# AFM_Power_board__NEW.net
KiCad netlist of a schematic drawn in EAGLE
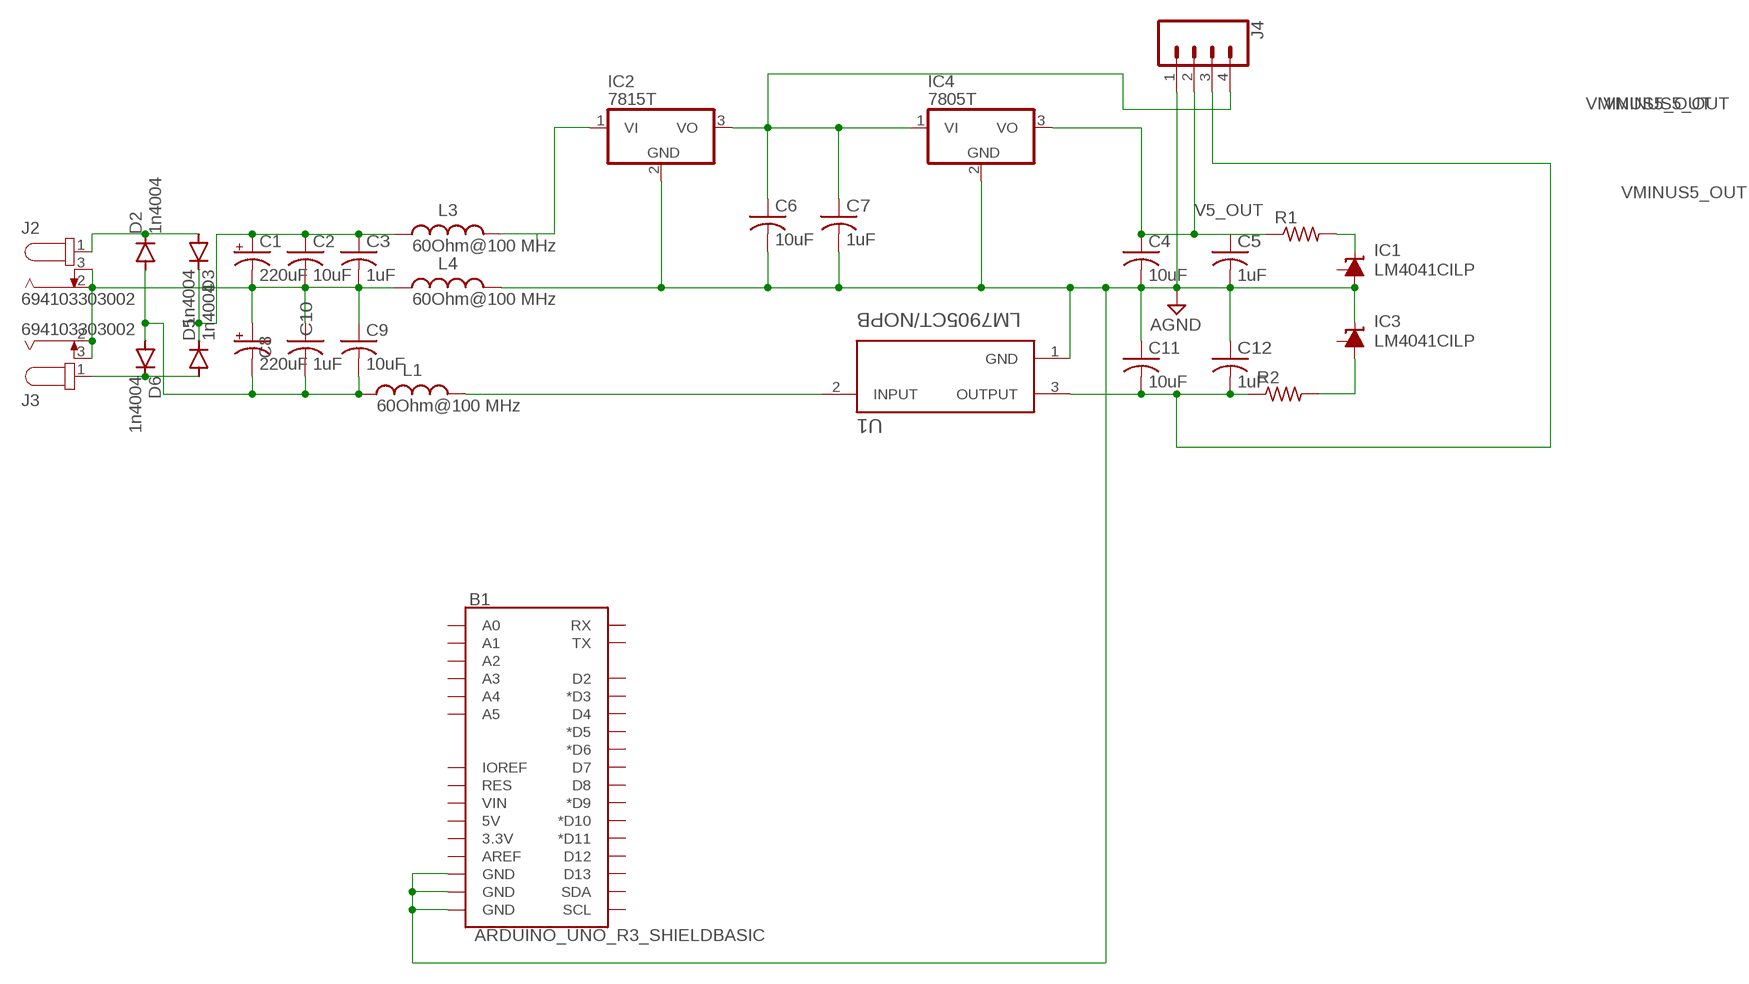
[diagram p0: schematic, sheet 1]

(export (version "E")
  (design (tool "Eeschema 10.0.6"))
  (components
    (comp (ref "B1")
      (value "ARDUINO_UNO_R3_SHIELDBASIC")
      (footprint "eagle-import:UNO_R3_SHIELD")
      (libsource (lib "eagle-import") (part "ARDUINO_UNO_R3_SHIELDBASIC"))
    )
    (comp (ref "C1")
      (value "220uF")
      (footprint "eagle-import:E5-8,5")
      (libsource (lib "eagle-import") (part "CAPACITOR-PE5-8.5"))
    )
    (comp (ref "C2")
      (value "10uF")
      (footprint "eagle-import:C050-024X044")
      (libsource (lib "eagle-import") (part "C-US050-024X044"))
    )
    (comp (ref "C3")
      (value "1uF")
      (footprint "eagle-import:C050-024X044")
      (libsource (lib "eagle-import") (part "C-US050-024X044"))
    )
    (comp (ref "C4")
      (value "10uF")
      (footprint "eagle-import:C050-024X044")
      (libsource (lib "eagle-import") (part "C-US050-024X044"))
    )
    (comp (ref "C5")
      (value "1uF")
      (footprint "eagle-import:C050-024X044")
      (libsource (lib "eagle-import") (part "C-US050-024X044"))
    )
    (comp (ref "C6")
      (value "10uF")
      (footprint "eagle-import:C050-024X044")
      (libsource (lib "eagle-import") (part "C-US050-024X044"))
    )
    (comp (ref "C7")
      (value "1uF")
      (footprint "eagle-import:C050-024X044")
      (libsource (lib "eagle-import") (part "C-US050-024X044"))
    )
    (comp (ref "C8")
      (value "220uF")
      (footprint "eagle-import:E5-8,5")
      (libsource (lib "eagle-import") (part "CAPACITOR-PE5-8.5"))
    )
    (comp (ref "C9")
      (value "10uF")
      (footprint "eagle-import:C050-024X044")
      (libsource (lib "eagle-import") (part "C-US050-024X044"))
    )
    (comp (ref "C10")
      (value "1uF")
      (footprint "eagle-import:C050-024X044")
      (libsource (lib "eagle-import") (part "C-US050-024X044"))
    )
    (comp (ref "C11")
      (value "10uF")
      (footprint "eagle-import:C050-024X044")
      (libsource (lib "eagle-import") (part "C-US050-024X044"))
    )
    (comp (ref "C12")
      (value "1uF")
      (footprint "eagle-import:C050-024X044")
      (libsource (lib "eagle-import") (part "C-US050-024X044"))
    )
    (comp (ref "D2")
      (value "1n4004")
      (footprint "eagle-import:SOD123")
      (libsource (lib "eagle-import") (part "DIODE-SOD123"))
    )
    (comp (ref "D3")
      (value "1n4004")
      (footprint "eagle-import:SOD123")
      (libsource (lib "eagle-import") (part "DIODE-SOD123"))
    )
    (comp (ref "D5")
      (value "1n4004")
      (footprint "eagle-import:SOD123")
      (libsource (lib "eagle-import") (part "DIODE-SOD123"))
    )
    (comp (ref "D6")
      (value "1n4004")
      (footprint "eagle-import:SOD123")
      (libsource (lib "eagle-import") (part "DIODE-SOD123"))
    )
    (comp (ref "IC1")
      (value "LM4041CILP")
      (footprint "eagle-import:LP_O-PBCY-W3")
      (libsource (lib "eagle-import") (part "LM4041ILPC"))
    )
    (comp (ref "IC2")
      (value "7815T")
      (footprint "eagle-import:TO220H")
      (libsource (lib "eagle-import") (part "78T15"))
    )
    (comp (ref "IC3")
      (value "LM4041CILP")
      (footprint "eagle-import:LP_O-PBCY-W3")
      (libsource (lib "eagle-import") (part "LM4041ILPC"))
    )
    (comp (ref "IC4")
      (value "7805T")
      (footprint "eagle-import:TO220H")
      (libsource (lib "eagle-import") (part "78T05"))
    )
    (comp (ref "J2")
      (value "694103303002")
      (footprint "eagle-import:694103303002")
      (fields
        (field (name "DIGIKEY_PART_NUMBER") "732-5925-ND")
        (field (name "MANUFACTURER") "Wurth Electronics Inc.")
        (field (name "CREATED_BY") "PCBLayout.com")
      )
      (libsource (lib "eagle-import") (part "694103303002"))
    )
    (comp (ref "J3")
      (value "694103303002")
      (footprint "eagle-import:694103303002")
      (fields
        (field (name "DIGIKEY_PART_NUMBER") "732-5925-ND")
        (field (name "MANUFACTURER") "Wurth Electronics Inc.")
        (field (name "CREATED_BY") "PCBLayout.com")
      )
      (libsource (lib "eagle-import") (part "694103303002"))
    )
    (comp (ref "J4")
      (value "CONN_04LONGPADS")
      (footprint "eagle-import:1X04_LONGPADS")
      (libsource (lib "eagle-import") (part "CONN_04LONGPADS"))
    )
    (comp (ref "L1")
      (value "60Ohm@100 MHz")
      (footprint "eagle-import:WE-CBF_0603_W2.2")
      (libsource (lib "eagle-import") (part "WE-CBF_0603_WB_HS_74279267"))
    )
    (comp (ref "L3")
      (value "60Ohm@100 MHz")
      (footprint "eagle-import:WE-CBF_0603_W2.2")
      (libsource (lib "eagle-import") (part "WE-CBF_0603_WB_HS_74279267"))
    )
    (comp (ref "L4")
      (value "60Ohm@100 MHz")
      (footprint "eagle-import:WE-CBF_0603_W2.2")
      (libsource (lib "eagle-import") (part "WE-CBF_0603_WB_HS_74279267"))
    )
    (comp (ref "R1")
      (value "R-US_0204/5")
      (footprint "eagle-import:0204_5")
      (libsource (lib "eagle-import") (part "R-US_0204/5"))
    )
    (comp (ref "R2")
      (value "R-US_0204/5")
      (footprint "eagle-import:0204_5")
      (libsource (lib "eagle-import") (part "R-US_0204/5"))
    )
    (comp (ref "U1")
      (value "LM7905CT/NOPB")
      (footprint "eagle-import:TO254P1016X4575X1955-3")
      (fields (field (name "MF") "Texas Instruments"))
      (libsource (lib "eagle-import") (part "LM7905CT/NOPB"))
    )
  )
  (nets
    (net (code "1") (name "/V5_OUT") (class "Default")
      (node (ref "C4") (pin "1") (pinfunction "1_1") (pintype "passive"))
      (node (ref "C5") (pin "1") (pinfunction "1_1") (pintype "passive"))
      (node (ref "IC4") (pin "3") (pinfunction "VO_3") (pintype "passive"))
      (node (ref "J4") (pin "2") (pinfunction "2_2") (pintype "passive"))
      (node (ref "R1") (pin "1") (pinfunction "1_1") (pintype "passive"))
    )
    (net (code "2") (name "/VMINUS5_OUT") (class "Default")
      (node (ref "C11") (pin "2") (pinfunction "2_2") (pintype "passive"))
      (node (ref "C12") (pin "2") (pinfunction "2_2") (pintype "passive"))
      (node (ref "J4") (pin "3") (pinfunction "3_3") (pintype "passive"))
      (node (ref "R2") (pin "1") (pinfunction "1_1") (pintype "passive"))
      (node (ref "U1") (pin "3") (pinfunction "OUTPUT_3") (pintype "output"))
    )
    (net (code "3") (name "AGND") (class "Default")
      (node (ref "B1") (pin "GND@0") (pinfunction "GND_GND@0") (pintype "bidirectional"))
      (node (ref "B1") (pin "GND@1") (pinfunction "GND_GND@1") (pintype "bidirectional"))
      (node (ref "B1") (pin "GND@2") (pinfunction "GND_GND@2") (pintype "bidirectional"))
      (node (ref "C11") (pin "1") (pinfunction "1_1") (pintype "passive"))
      (node (ref "C12") (pin "1") (pinfunction "1_1") (pintype "passive"))
      (node (ref "C4") (pin "2") (pinfunction "2_2") (pintype "passive"))
      (node (ref "C5") (pin "2") (pinfunction "2_2") (pintype "passive"))
      (node (ref "C6") (pin "2") (pinfunction "2_2") (pintype "passive"))
      (node (ref "C7") (pin "2") (pinfunction "2_2") (pintype "passive"))
      (node (ref "IC1") (pin "3") (pinfunction "A_3") (pintype "passive"))
      (node (ref "IC2") (pin "2") (pinfunction "GND_2") (pintype "passive"))
      (node (ref "IC3") (pin "2") (pinfunction "C_2") (pintype "passive"))
      (node (ref "IC4") (pin "2") (pinfunction "GND_2") (pintype "passive"))
      (node (ref "J4") (pin "1") (pinfunction "1_1") (pintype "passive"))
      (node (ref "L4") (pin "2") (pinfunction "2_2") (pintype "passive"))
      (node (ref "U1") (pin "1") (pinfunction "GND_1") (pintype "power_in"))
    )
    (net (code "4") (name "Net-(C1-Pad+)") (class "Default")
      (node (ref "C1") (pin "+") (pinfunction "+_+") (pintype "passive"))
      (node (ref "C2") (pin "1") (pinfunction "1_1") (pintype "passive"))
      (node (ref "C3") (pin "1") (pinfunction "1_1") (pintype "passive"))
      (node (ref "D3") (pin "C") (pinfunction "C_C") (pintype "passive"))
      (node (ref "D5") (pin "C") (pinfunction "C_C") (pintype "passive"))
      (node (ref "L3") (pin "1") (pinfunction "1_1") (pintype "passive"))
    )
    (net (code "5") (name "Net-(C1-Pad-)") (class "Default")
      (node (ref "C1") (pin "-") (pinfunction "-_-") (pintype "passive"))
      (node (ref "C10") (pin "1") (pinfunction "1_1") (pintype "passive"))
      (node (ref "C2") (pin "2") (pinfunction "2_2") (pintype "passive"))
      (node (ref "C3") (pin "2") (pinfunction "2_2") (pintype "passive"))
      (node (ref "C8") (pin "+") (pinfunction "+_+") (pintype "passive"))
      (node (ref "C9") (pin "1") (pinfunction "1_1") (pintype "passive"))
      (node (ref "J2") (pin "2") (pinfunction "2_2") (pintype "passive"))
      (node (ref "J2") (pin "3") (pinfunction "3_3") (pintype "passive"))
      (node (ref "J3") (pin "2") (pinfunction "2_2") (pintype "passive"))
      (node (ref "J3") (pin "3") (pinfunction "3_3") (pintype "passive"))
      (node (ref "L4") (pin "1") (pinfunction "1_1") (pintype "passive"))
    )
    (net (code "6") (name "Net-(C10-Pad2)") (class "Default")
      (node (ref "C10") (pin "2") (pinfunction "2_2") (pintype "passive"))
      (node (ref "C8") (pin "-") (pinfunction "-_-") (pintype "passive"))
      (node (ref "C9") (pin "2") (pinfunction "2_2") (pintype "passive"))
      (node (ref "D2") (pin "A") (pinfunction "A_A") (pintype "passive"))
      (node (ref "D6") (pin "A") (pinfunction "A_A") (pintype "passive"))
      (node (ref "L1") (pin "1") (pinfunction "1_1") (pintype "passive"))
    )
    (net (code "7") (name "Net-(D2-PadC)") (class "Default")
      (node (ref "D2") (pin "C") (pinfunction "C_C") (pintype "passive"))
      (node (ref "D3") (pin "A") (pinfunction "A_A") (pintype "passive"))
      (node (ref "J2") (pin "1") (pinfunction "1_1") (pintype "passive"))
    )
    (net (code "8") (name "Net-(D5-PadA)") (class "Default")
      (node (ref "D5") (pin "A") (pinfunction "A_A") (pintype "passive"))
      (node (ref "D6") (pin "C") (pinfunction "C_C") (pintype "passive"))
      (node (ref "J3") (pin "1") (pinfunction "1_1") (pintype "passive"))
    )
    (net (code "9") (name "Net-(IC1-C)") (class "Default")
      (node (ref "IC1") (pin "2") (pinfunction "C_2") (pintype "passive"))
      (node (ref "R1") (pin "2") (pinfunction "2_2") (pintype "passive"))
    )
    (net (code "10") (name "Net-(IC2-VI)") (class "Default")
      (node (ref "IC2") (pin "1") (pinfunction "VI_1") (pintype "input"))
      (node (ref "L3") (pin "2") (pinfunction "2_2") (pintype "passive"))
    )
    (net (code "11") (name "Net-(IC2-VO)") (class "Default")
      (node (ref "C6") (pin "1") (pinfunction "1_1") (pintype "passive"))
      (node (ref "C7") (pin "1") (pinfunction "1_1") (pintype "passive"))
      (node (ref "IC2") (pin "3") (pinfunction "VO_3") (pintype "passive"))
      (node (ref "IC4") (pin "1") (pinfunction "VI_1") (pintype "input"))
      (node (ref "J4") (pin "4") (pinfunction "4_4") (pintype "passive"))
    )
    (net (code "12") (name "Net-(IC3-A)") (class "Default")
      (node (ref "IC3") (pin "3") (pinfunction "A_3") (pintype "passive"))
      (node (ref "R2") (pin "2") (pinfunction "2_2") (pintype "passive"))
    )
    (net (code "13") (name "Net-(U1-INPUT)") (class "Default")
      (node (ref "L1") (pin "2") (pinfunction "2_2") (pintype "passive"))
      (node (ref "U1") (pin "2") (pinfunction "INPUT_2") (pintype "input"))
    )
    (net (code "14") (name "unconnected-(B1-*D3-PadD3)") (class "Default")
      (node (ref "B1") (pin "D3") (pinfunction "*D3_D3") (pintype "bidirectional"))
    )
    (net (code "15") (name "unconnected-(B1-*D5-PadD5)") (class "Default")
      (node (ref "B1") (pin "D5") (pinfunction "*D5_D5") (pintype "bidirectional"))
    )
    (net (code "16") (name "unconnected-(B1-*D6-PadD6)") (class "Default")
      (node (ref "B1") (pin "D6") (pinfunction "*D6_D6") (pintype "bidirectional"))
    )
    (net (code "17") (name "unconnected-(B1-*D9-PadD9)") (class "Default")
      (node (ref "B1") (pin "D9") (pinfunction "*D9_D9") (pintype "bidirectional"))
    )
    (net (code "18") (name "unconnected-(B1-*D10-PadD10)") (class "Default")
      (node (ref "B1") (pin "D10") (pinfunction "*D10_D10") (pintype "bidirectional"))
    )
    (net (code "19") (name "unconnected-(B1-*D11-PadD11)") (class "Default")
      (node (ref "B1") (pin "D11") (pinfunction "*D11_D11") (pintype "bidirectional"))
    )
    (net (code "20") (name "unconnected-(B1-Pad3.3V)") (class "Default")
      (node (ref "B1") (pin "3.3V") (pinfunction "3.3V_3.3V") (pintype "bidirectional"))
    )
    (net (code "21") (name "unconnected-(B1-Pad5V)") (class "Default")
      (node (ref "B1") (pin "5V") (pinfunction "5V_5V") (pintype "bidirectional"))
    )
    (net (code "22") (name "unconnected-(B1-PadA0)") (class "Default")
      (node (ref "B1") (pin "A0") (pinfunction "A0_A0") (pintype "bidirectional"))
    )
    (net (code "23") (name "unconnected-(B1-PadA1)") (class "Default")
      (node (ref "B1") (pin "A1") (pinfunction "A1_A1") (pintype "bidirectional"))
    )
    (net (code "24") (name "unconnected-(B1-PadA2)") (class "Default")
      (node (ref "B1") (pin "A2") (pinfunction "A2_A2") (pintype "bidirectional"))
    )
    (net (code "25") (name "unconnected-(B1-PadA3)") (class "Default")
      (node (ref "B1") (pin "A3") (pinfunction "A3_A3") (pintype "bidirectional"))
    )
    (net (code "26") (name "unconnected-(B1-PadA4)") (class "Default")
      (node (ref "B1") (pin "A4") (pinfunction "A4_A4") (pintype "bidirectional"))
    )
    (net (code "27") (name "unconnected-(B1-PadA5)") (class "Default")
      (node (ref "B1") (pin "A5") (pinfunction "A5_A5") (pintype "bidirectional"))
    )
    (net (code "28") (name "unconnected-(B1-PadAREF)") (class "Default")
      (node (ref "B1") (pin "AREF") (pinfunction "AREF_AREF") (pintype "bidirectional"))
    )
    (net (code "29") (name "unconnected-(B1-PadD2)") (class "Default")
      (node (ref "B1") (pin "D2") (pinfunction "D2_D2") (pintype "bidirectional"))
    )
    (net (code "30") (name "unconnected-(B1-PadD4)") (class "Default")
      (node (ref "B1") (pin "D4") (pinfunction "D4_D4") (pintype "bidirectional"))
    )
    (net (code "31") (name "unconnected-(B1-PadD7)") (class "Default")
      (node (ref "B1") (pin "D7") (pinfunction "D7_D7") (pintype "bidirectional"))
    )
    (net (code "32") (name "unconnected-(B1-PadD8)") (class "Default")
      (node (ref "B1") (pin "D8") (pinfunction "D8_D8") (pintype "bidirectional"))
    )
    (net (code "33") (name "unconnected-(B1-PadD12)") (class "Default")
      (node (ref "B1") (pin "D12") (pinfunction "D12_D12") (pintype "bidirectional"))
    )
    (net (code "34") (name "unconnected-(B1-PadD13)") (class "Default")
      (node (ref "B1") (pin "D13") (pinfunction "D13_D13") (pintype "bidirectional"))
    )
    (net (code "35") (name "unconnected-(B1-PadIOREF)") (class "Default")
      (node (ref "B1") (pin "IOREF") (pinfunction "IOREF_IOREF") (pintype "bidirectional"))
    )
    (net (code "36") (name "unconnected-(B1-PadRES)") (class "Default")
      (node (ref "B1") (pin "RES") (pinfunction "RES_RES") (pintype "bidirectional"))
    )
    (net (code "37") (name "unconnected-(B1-PadRX)") (class "Default")
      (node (ref "B1") (pin "RX") (pinfunction "RX_RX") (pintype "bidirectional"))
    )
    (net (code "38") (name "unconnected-(B1-PadSCL)") (class "Default")
      (node (ref "B1") (pin "SCL") (pinfunction "SCL_SCL") (pintype "bidirectional"))
    )
    (net (code "39") (name "unconnected-(B1-PadSDA)") (class "Default")
      (node (ref "B1") (pin "SDA") (pinfunction "SDA_SDA") (pintype "bidirectional"))
    )
    (net (code "40") (name "unconnected-(B1-PadTX)") (class "Default")
      (node (ref "B1") (pin "TX") (pinfunction "TX_TX") (pintype "bidirectional"))
    )
    (net (code "41") (name "unconnected-(B1-PadVIN)") (class "Default")
      (node (ref "B1") (pin "VIN") (pinfunction "VIN_VIN") (pintype "bidirectional"))
    )
    (net (code "42") (name "unconnected-(IC1-FB-Pad1)") (class "Default")
      (node (ref "IC1") (pin "1") (pinfunction "FB_1") (pintype "passive"))
    )
    (net (code "43") (name "unconnected-(IC3-FB-Pad1)") (class "Default")
      (node (ref "IC3") (pin "1") (pinfunction "FB_1") (pintype "passive"))
    )
  )
)
